# 02_Power.net
KiCad netlist of a schematic drawn in Altium Designer
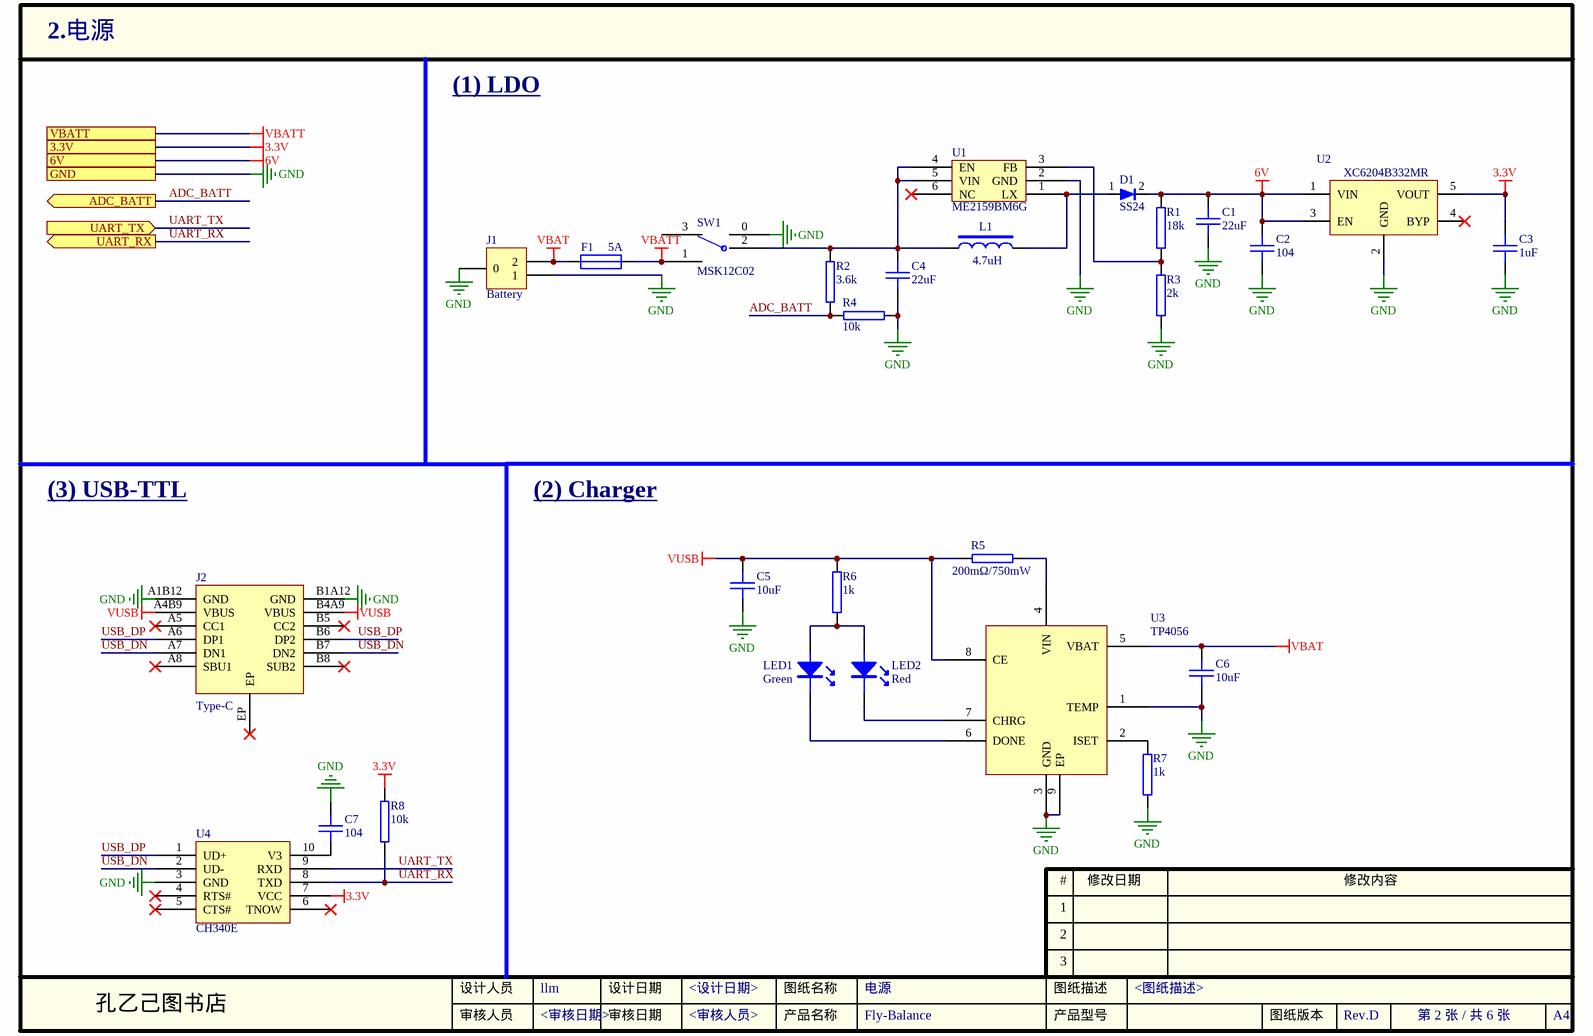
[diagram p0: 02_Power.SchDoc]

(export (version "E")
  (design (tool "Eeschema 10.0.6"))
  (components
    (comp (ref "C1")
      (value "22uF")
      (footprint "0805C")
      (description "电容")
      (libsource (lib "MY_Schlib") (part "CAP"))
    )
    (comp (ref "C2")
      (value "104")
      (footprint "0402C")
      (description "电容")
      (libsource (lib "MY_Schlib") (part "CAP"))
    )
    (comp (ref "C3")
      (value "1uF")
      (footprint "0402C")
      (description "电容")
      (libsource (lib "MY_Schlib") (part "CAP"))
    )
    (comp (ref "C4")
      (value "22uF")
      (footprint "0805C")
      (description "电容")
      (libsource (lib "MY_Schlib") (part "CAP"))
    )
    (comp (ref "C5")
      (value "10uF")
      (footprint "0805C")
      (description "电容")
      (libsource (lib "MY_Schlib") (part "CAP"))
    )
    (comp (ref "C6")
      (value "10uF")
      (footprint "0805C")
      (description "电容")
      (libsource (lib "MY_Schlib") (part "CAP"))
    )
    (comp (ref "C7")
      (value "104")
      (footprint "0402C")
      (description "电容")
      (libsource (lib "MY_Schlib") (part "CAP"))
    )
    (comp (ref "D1")
      (value "SS24")
      (footprint "SMA_L4.3-W2.5-LS5.0-RD")
      (description "二极管")
      (libsource (lib "MY_Schlib") (part "DIODE"))
    )
    (comp (ref "F1")
      (value "5A")
      (footprint "1206R")
      (description "保险丝")
      (libsource (lib "MY_Schlib") (part "Fuse"))
    )
    (comp (ref "J1")
      (value "Battery")
      (footprint "51005母座")
      (description "直流电机接口")
      (libsource (lib "Schlib") (part "CON"))
    )
    (comp (ref "J2")
      (value "Type-C")
      (footprint "USB-C-SMD_TYPE-C-16P-1")
      (libsource (lib "MY_Schlib") (part "Type-C"))
    )
    (comp (ref "L1")
      (value "4.7uH")
      (footprint "IND-SMD_L5.0-W5.0_FNR50XXS")
      (description "电感")
      (libsource (lib "MY_Schlib") (part "INDUCTOR_2"))
    )
    (comp (ref "LED1")
      (value "Green")
      (footprint "LED-0603")
      (description "发光二极管")
      (libsource (lib "MY_Schlib") (part "LED"))
    )
    (comp (ref "LED2")
      (value "Red")
      (footprint "LED-0603")
      (description "发光二极管")
      (libsource (lib "MY_Schlib") (part "LED"))
    )
    (comp (ref "R1")
      (value "18k")
      (footprint "0402R")
      (description "电阻")
      (libsource (lib "MY_Schlib") (part "RES"))
    )
    (comp (ref "R2")
      (value "3.6k")
      (footprint "0402R")
      (description "电阻")
      (libsource (lib "MY_Schlib") (part "RES"))
    )
    (comp (ref "R3")
      (value "2k")
      (footprint "0402R")
      (description "电阻")
      (libsource (lib "MY_Schlib") (part "RES"))
    )
    (comp (ref "R4")
      (value "10k")
      (footprint "0402R")
      (description "电阻")
      (libsource (lib "MY_Schlib") (part "RES"))
    )
    (comp (ref "R5")
      (value "200mΩ/750mW")
      (footprint "2010R")
      (description "电阻")
      (libsource (lib "MY_Schlib") (part "RES"))
    )
    (comp (ref "R6")
      (value "1k")
      (footprint "0402R")
      (description "电阻")
      (libsource (lib "MY_Schlib") (part "RES"))
    )
    (comp (ref "R7")
      (value "1k")
      (footprint "0402R")
      (description "电阻")
      (libsource (lib "MY_Schlib") (part "RES"))
    )
    (comp (ref "R8")
      (value "10k")
      (footprint "0402R")
      (description "电阻")
      (libsource (lib "MY_Schlib") (part "RES"))
    )
    (comp (ref "SW1") (value "MSK12C02") (footprint "MSK12C02") (libsource (lib "Schlib") (part "单刀双掷开关")))
    (comp (ref "U1")
      (value "ME2159BM6G")
      (footprint "SOT-23-6_L2.9-W1.6-P0.95-LS2.8-BR")
      (description "DC-DC升压芯片")
      (libsource (lib "MY_Schlib") (part "ME2159BM6G"))
    )
    (comp (ref "U2")
      (value "XC6204B332MR")
      (footprint "SOT-23-5")
      (description "LDO, 3.0V输出")
      (libsource (lib "MY_Schlib") (part "ZL6205A30TS5"))
    )
    (comp (ref "U3")
      (value "TP4056")
      (footprint "ESOP-8_L4.9-W3.9-P1.27-LS6.0-BL-EP")
      (description "单节锂电池充电芯片")
      (libsource (lib "MY_Schlib") (part "4056"))
    )
    (comp (ref "U4")
      (value "CH340E")
      (footprint "MSOP-10_L3.0-W3.0-P0.50-LS5.0-BL")
      (description "USB-TTL芯片")
      (libsource (lib "MY_Schlib") (part "CH340E"))
    )
  )
  (nets
    (net (code "1") (name "/ADC_BATT") (class "Default")
      (node (ref "R2") (pin "1") (pinfunction "1_1") (pintype "passive"))
      (node (ref "R4") (pin "2") (pinfunction "2_2") (pintype "passive"))
    )
    (net (code "2") (name "/UART_RX") (class "Default")
      (node (ref "R8") (pin "1") (pinfunction "1_1") (pintype "passive"))
      (node (ref "U4") (pin "8") (pinfunction "TXD_8") (pintype "passive"))
    )
    (net (code "3") (name "/UART_TX") (class "Default")
      (node (ref "U4") (pin "9") (pinfunction "RXD_9") (pintype "passive"))
    )
    (net (code "4") (name "/USB_DN") (class "Default")
      (node (ref "J2") (pin "A7") (pinfunction "DN1_A7") (pintype "passive"))
      (node (ref "J2") (pin "B7") (pinfunction "DN2_B7") (pintype "passive"))
      (node (ref "U4") (pin "2") (pinfunction "UD-_2") (pintype "passive"))
    )
    (net (code "5") (name "/USB_DP") (class "Default")
      (node (ref "J2") (pin "A6") (pinfunction "DP1_A6") (pintype "passive"))
      (node (ref "J2") (pin "B6") (pinfunction "DP2_B6") (pintype "passive"))
      (node (ref "U4") (pin "1") (pinfunction "UD+_1") (pintype "passive"))
    )
    (net (code "6") (name "3.3V") (class "Default")
      (node (ref "C3") (pin "1") (pinfunction "1_1") (pintype "passive"))
      (node (ref "R8") (pin "2") (pinfunction "2_2") (pintype "passive"))
      (node (ref "U2") (pin "5") (pinfunction "VOUT_5") (pintype "passive"))
      (node (ref "U4") (pin "7") (pinfunction "VCC_7") (pintype "passive"))
    )
    (net (code "7") (name "6V") (class "Default")
      (node (ref "C1") (pin "1") (pinfunction "1_1") (pintype "passive"))
      (node (ref "C2") (pin "1") (pinfunction "1_1") (pintype "passive"))
      (node (ref "D1") (pin "2") (pinfunction "2_2") (pintype "passive"))
      (node (ref "R1") (pin "2") (pinfunction "2_2") (pintype "passive"))
      (node (ref "U2") (pin "1") (pinfunction "VIN_1") (pintype "passive"))
      (node (ref "U2") (pin "3") (pinfunction "EN_3") (pintype "passive"))
    )
    (net (code "8") (name "GND") (class "Default")
      (node (ref "C1") (pin "2") (pinfunction "2_2") (pintype "passive"))
      (node (ref "C2") (pin "2") (pinfunction "2_2") (pintype "passive"))
      (node (ref "C3") (pin "2") (pinfunction "2_2") (pintype "passive"))
      (node (ref "C4") (pin "2") (pinfunction "2_2") (pintype "passive"))
      (node (ref "C5") (pin "2") (pinfunction "2_2") (pintype "passive"))
      (node (ref "C6") (pin "2") (pinfunction "2_2") (pintype "passive"))
      (node (ref "C7") (pin "2") (pinfunction "2_2") (pintype "passive"))
      (node (ref "J1") (pin "0") (pinfunction "0_0") (pintype "passive"))
      (node (ref "J1") (pin "1") (pinfunction "1_1") (pintype "passive"))
      (node (ref "J2") (pin "A1B12") (pinfunction "GND_A1B12") (pintype "passive"))
      (node (ref "J2") (pin "B1A12") (pinfunction "GND_B1A12") (pintype "passive"))
      (node (ref "R3") (pin "1") (pinfunction "1_1") (pintype "passive"))
      (node (ref "R4") (pin "1") (pinfunction "1_1") (pintype "passive"))
      (node (ref "R7") (pin "1") (pinfunction "1_1") (pintype "passive"))
      (node (ref "SW1") (pin "0") (pinfunction "0_0") (pintype "power_in"))
      (node (ref "U1") (pin "2") (pinfunction "GND_2") (pintype "passive"))
      (node (ref "U2") (pin "2") (pinfunction "GND_2") (pintype "passive"))
      (node (ref "U3") (pin "1") (pinfunction "TEMP_1") (pintype "passive"))
      (node (ref "U3") (pin "3") (pinfunction "GND_3") (pintype "passive"))
      (node (ref "U3") (pin "9") (pinfunction "EP_9") (pintype "passive"))
      (node (ref "U4") (pin "3") (pinfunction "GND_3") (pintype "passive"))
    )
    (net (code "9") (name "Net-(LED1-Pad1)") (class "Default")
      (node (ref "LED1") (pin "1") (pinfunction "1_1") (pintype "passive"))
      (node (ref "LED2") (pin "1") (pinfunction "1_1") (pintype "passive"))
      (node (ref "R6") (pin "1") (pinfunction "1_1") (pintype "passive"))
    )
    (net (code "10") (name "Net-(U1-EN)") (class "Default")
      (node (ref "C4") (pin "1") (pinfunction "1_1") (pintype "passive"))
      (node (ref "L1") (pin "1") (pinfunction "1_1") (pintype "passive"))
      (node (ref "R2") (pin "2") (pinfunction "2_2") (pintype "passive"))
      (node (ref "SW1") (pin "2") (pinfunction "2_2") (pintype "power_in"))
      (node (ref "U1") (pin "4") (pinfunction "EN_4") (pintype "passive"))
      (node (ref "U1") (pin "5") (pinfunction "VIN_5") (pintype "passive"))
    )
    (net (code "11") (name "Net-(U1-FB)") (class "Default")
      (node (ref "R1") (pin "1") (pinfunction "1_1") (pintype "passive"))
      (node (ref "R3") (pin "2") (pinfunction "2_2") (pintype "passive"))
      (node (ref "U1") (pin "3") (pinfunction "FB_3") (pintype "passive"))
    )
    (net (code "12") (name "Net-(U1-LX)") (class "Default")
      (node (ref "D1") (pin "1") (pinfunction "1_1") (pintype "passive"))
      (node (ref "L1") (pin "2") (pinfunction "2_2") (pintype "passive"))
      (node (ref "U1") (pin "1") (pinfunction "LX_1") (pintype "passive"))
    )
    (net (code "13") (name "Net-(U3-CHRG)") (class "Default")
      (node (ref "LED2") (pin "2") (pinfunction "2_2") (pintype "passive"))
      (node (ref "U3") (pin "7") (pinfunction "CHRG_7") (pintype "passive"))
    )
    (net (code "14") (name "Net-(U3-DONE)") (class "Default")
      (node (ref "LED1") (pin "2") (pinfunction "2_2") (pintype "passive"))
      (node (ref "U3") (pin "6") (pinfunction "DONE_6") (pintype "passive"))
    )
    (net (code "15") (name "Net-(U3-ISET)") (class "Default")
      (node (ref "R7") (pin "2") (pinfunction "2_2") (pintype "passive"))
      (node (ref "U3") (pin "2") (pinfunction "ISET_2") (pintype "passive"))
    )
    (net (code "16") (name "Net-(U3-VIN)") (class "Default")
      (node (ref "R5") (pin "1") (pinfunction "1_1") (pintype "passive"))
      (node (ref "U3") (pin "4") (pinfunction "VIN_4") (pintype "passive"))
    )
    (net (code "17") (name "Net-(U4-V3)") (class "Default")
      (node (ref "C7") (pin "1") (pinfunction "1_1") (pintype "passive"))
      (node (ref "U4") (pin "10") (pinfunction "V3_10") (pintype "passive"))
    )
    (net (code "18") (name "VBAT") (class "Default")
      (node (ref "C6") (pin "1") (pinfunction "1_1") (pintype "passive"))
      (node (ref "F1") (pin "2") (pinfunction "2_2") (pintype "passive"))
      (node (ref "J1") (pin "2") (pinfunction "2_2") (pintype "passive"))
      (node (ref "U3") (pin "5") (pinfunction "VBAT_5") (pintype "passive"))
    )
    (net (code "19") (name "VBATT") (class "Default")
      (node (ref "F1") (pin "1") (pinfunction "1_1") (pintype "passive"))
      (node (ref "SW1") (pin "1") (pinfunction "1_1") (pintype "power_in"))
    )
    (net (code "20") (name "VUSB") (class "Default")
      (node (ref "C5") (pin "1") (pinfunction "1_1") (pintype "passive"))
      (node (ref "J2") (pin "A4B9") (pinfunction "VBUS_A4B9") (pintype "passive"))
      (node (ref "J2") (pin "B4A9") (pinfunction "VBUS_B4A9") (pintype "passive"))
      (node (ref "R5") (pin "2") (pinfunction "2_2") (pintype "passive"))
      (node (ref "R6") (pin "2") (pinfunction "2_2") (pintype "passive"))
      (node (ref "U3") (pin "8") (pinfunction "CE_8") (pintype "passive"))
    )
    (net (code "21") (name "unconnected-(J2-CC1-PadA5)") (class "Default")
      (node (ref "J2") (pin "A5") (pinfunction "CC1_A5") (pintype "passive+no_connect"))
    )
    (net (code "22") (name "unconnected-(J2-CC2-PadB5)") (class "Default")
      (node (ref "J2") (pin "B5") (pinfunction "CC2_B5") (pintype "passive+no_connect"))
    )
    (net (code "23") (name "unconnected-(J2-PadEP)") (class "Default")
      (node (ref "J2") (pin "EP") (pinfunction "EP_EP") (pintype "passive+no_connect"))
    )
    (net (code "24") (name "unconnected-(J2-SBU1-PadA8)") (class "Default")
      (node (ref "J2") (pin "A8") (pinfunction "SBU1_A8") (pintype "passive+no_connect"))
    )
    (net (code "25") (name "unconnected-(J2-SUB2-PadB8)") (class "Default")
      (node (ref "J2") (pin "B8") (pinfunction "SUB2_B8") (pintype "passive+no_connect"))
    )
    (net (code "26") (name "unconnected-(SW1-Pad3)") (class "Default")
      (node (ref "SW1") (pin "3") (pinfunction "3_3") (pintype "power_in"))
    )
    (net (code "27") (name "unconnected-(U1-NC-Pad6)") (class "Default")
      (node (ref "U1") (pin "6") (pinfunction "NC_6") (pintype "passive+no_connect"))
    )
    (net (code "28") (name "unconnected-(U2-BYP-Pad4)") (class "Default")
      (node (ref "U2") (pin "4") (pinfunction "BYP_4") (pintype "passive+no_connect"))
    )
    (net (code "29") (name "unconnected-(U4-CTS#-Pad5)") (class "Default")
      (node (ref "U4") (pin "5") (pinfunction "CTS#_5") (pintype "passive+no_connect"))
    )
    (net (code "30") (name "unconnected-(U4-RTS#-Pad4)") (class "Default")
      (node (ref "U4") (pin "4") (pinfunction "RTS#_4") (pintype "passive+no_connect"))
    )
    (net (code "31") (name "unconnected-(U4-TNOW-Pad6)") (class "Default")
      (node (ref "U4") (pin "6") (pinfunction "TNOW_6") (pintype "passive+no_connect"))
    )
  )
)
